# Alimentation.net
KiCad netlist of a schematic drawn in Altium Designer
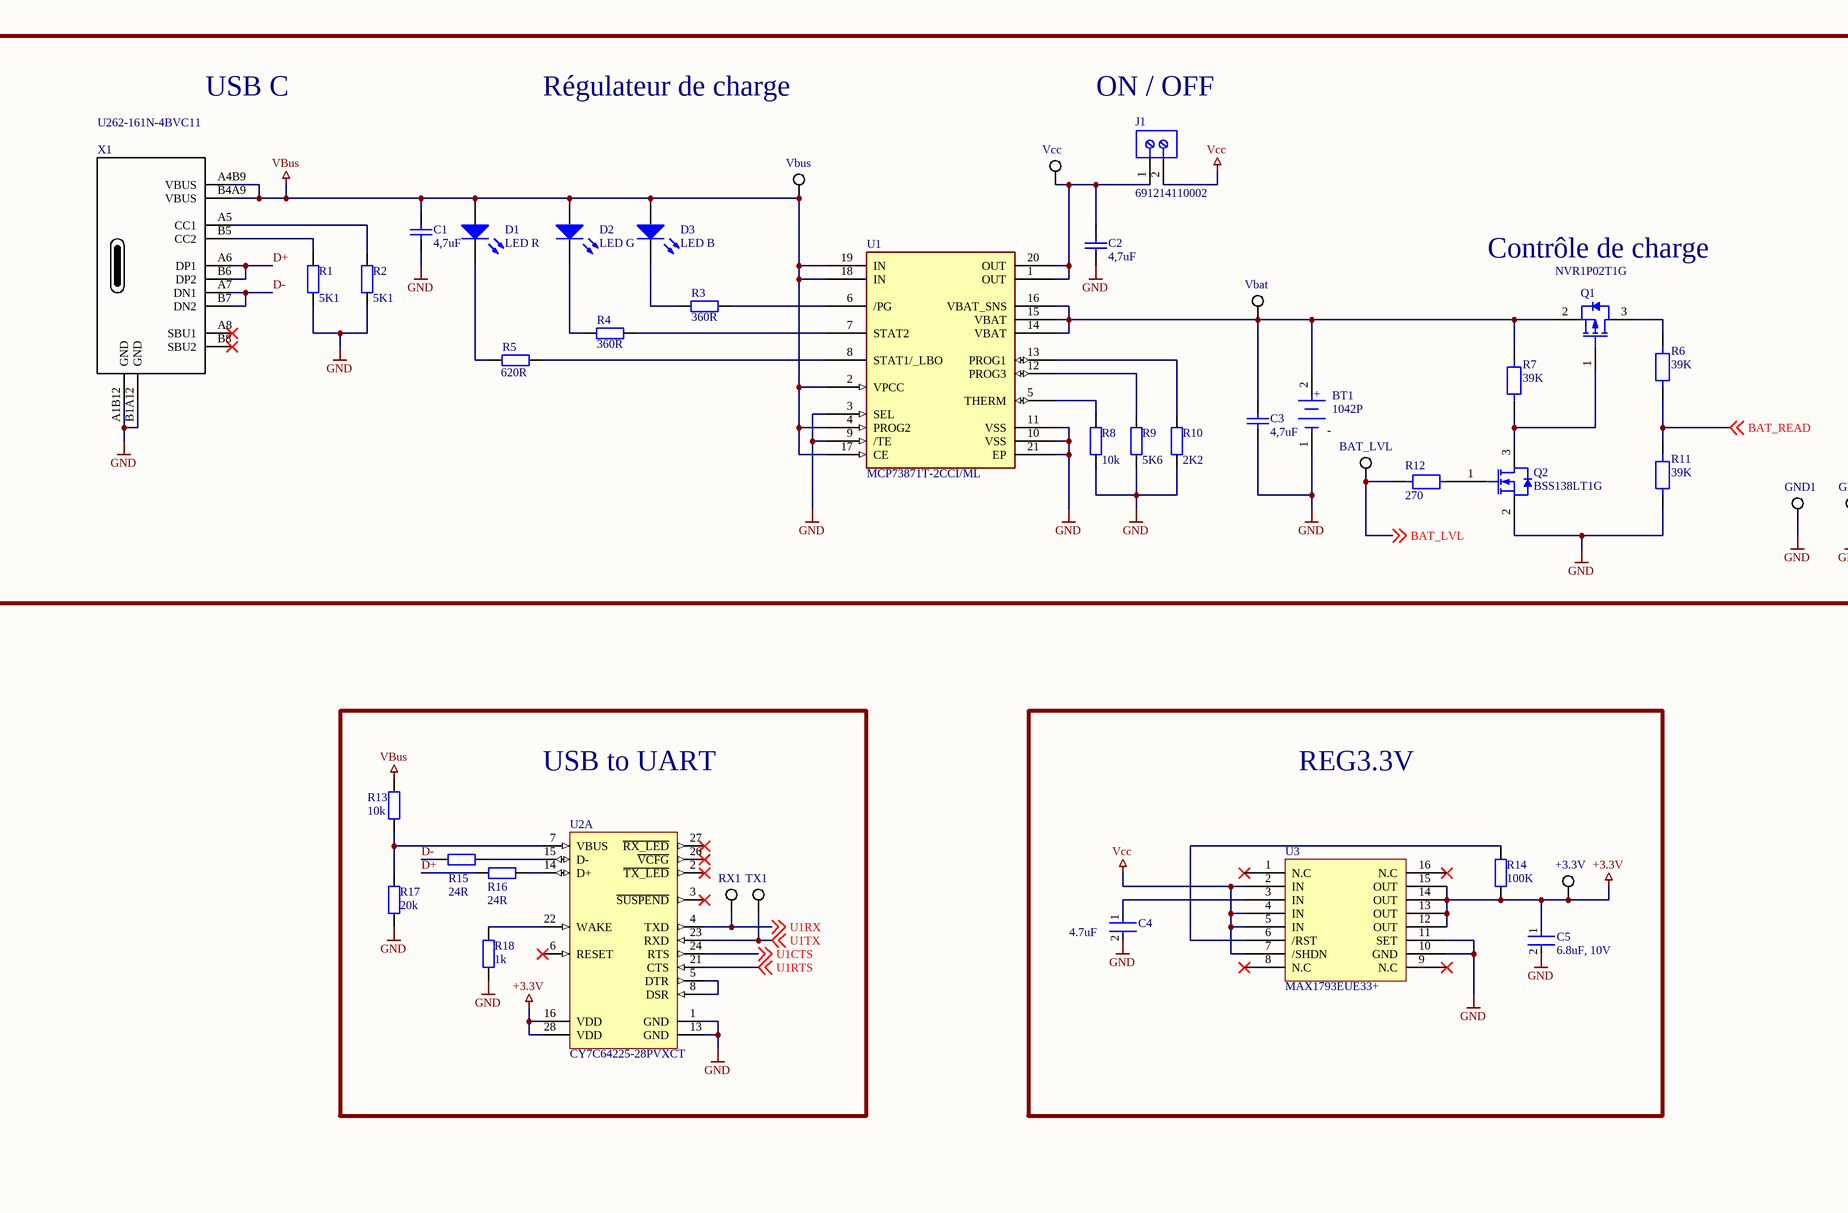
[diagram p0: Alimentation.SchDoc, left]
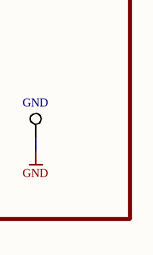
[diagram p1: Alimentation.SchDoc, right]

(export (version "E")
  (design (tool "Eeschema 10.0.6"))
  (components
    (comp (ref "+3.3V")
      (value "3.3V")
      (footprint "KSTN-5019_V")
      (description "Test Point, 1 Position SMD, RoHS, Tape and Reel")
      (libsource (lib "Altium Content Vault") (part "TESTPOINT_WHITE"))
    )
    (comp (ref "BAT_LVL")
      (value "Vbat")
      (footprint "KSTN-5019_V")
      (description "Test Point, 1 Position SMD, RoHS, Tape and Reel")
      (libsource (lib "Altium Content Vault") (part "TESTPOINT_WHITE"))
    )
    (comp (ref "BT1")
      (value "1042P")
      (footprint "FP-1042P-MFG")
      (description "BATTERY HOLDER 18650 SMD TAB")
      (libsource (lib "Altium Content Vault") (part "60d3b5b901a8747834971d0eb8cf3fd"))
    )
    (comp (ref "C1")
      (value "4,7uF")
      (footprint "CAP_0805")
      (description "Capacitor")
      (fields (field (name "PUBLISHER") "Altium Limited"))
      (libsource (lib "Miscellaneous Devices") (part "Cap"))
    )
    (comp (ref "C2")
      (value "4,7uF")
      (footprint "CAP_0805")
      (description "Capacitor")
      (fields (field (name "PUBLISHER") "Altium Limited"))
      (libsource (lib "Miscellaneous Devices") (part "Cap"))
    )
    (comp (ref "C3")
      (value "4,7uF")
      (footprint "CAP_0805")
      (description "Capacitor")
      (fields (field (name "PUBLISHER") "Altium Limited"))
      (libsource (lib "Miscellaneous Devices") (part "Cap"))
    )
    (comp (ref "C4")
      (value "4.7uF, 35V")
      (footprint "CAP_0805")
      (description "Multilayer Ceramic Capacitors 4.7μF ±10% 35V X7R SMD 0805")
      (fields (field (name "TOLERANCE") "10%") (field (name "CAPACITANCE") "4.7uF"))
      (libsource (lib "2121_Robot3roues_V2.0") (part "b4654b650e69147ec39a6b967a45e02"))
    )
    (comp (ref "C5")
      (value "6.8uF, 10V")
      (footprint "CAP_0805")
      (description "Cap Ceramic 6.8uF 10V X5R 20% Pad SMD 0805 +85°C Automotive T/R")
      (fields (field (name "TOLERANCE") "20%"))
      (libsource (lib "2121_Robot3roues_V2.0") (part "b4654b650e69147ec39a6b967a45e02"))
    )
    (comp (ref "D1")
      (value "LED R")
      (footprint "3.2X1.6X1.1")
      (description "Typical RED, GREEN, YELLOW, AMBER GaAs LED")
      (fields (field (name "PUBLISHER") "Altium Limited"))
      (libsource (lib "Miscellaneous Devices") (part "LED2"))
    )
    (comp (ref "D2")
      (value "LED G")
      (footprint "3.2X1.6X1.1")
      (description "Typical RED, GREEN, YELLOW, AMBER GaAs LED")
      (fields (field (name "PUBLISHER") "Altium Limited"))
      (libsource (lib "Miscellaneous Devices") (part "LED2"))
    )
    (comp (ref "D3")
      (value "LED B")
      (footprint "3.2X1.6X1.1")
      (description "Typical RED, GREEN, YELLOW, AMBER GaAs LED")
      (fields (field (name "PUBLISHER") "Altium Limited"))
      (libsource (lib "Miscellaneous Devices") (part "LED2"))
    )
    (comp (ref "GND")
      (value "Vbat")
      (footprint "KSTN-5019_V")
      (description "Test Point, 1 Position SMD, RoHS, Tape and Reel")
      (libsource (lib "Altium Content Vault") (part "TESTPOINT_WHITE"))
    )
    (comp (ref "GND1")
      (value "Vbat")
      (footprint "KSTN-5019_V")
      (description "Test Point, 1 Position SMD, RoHS, Tape and Reel")
      (libsource (lib "Altium Content Vault") (part "TESTPOINT_WHITE"))
    )
    (comp (ref "J1")
      (value "691214110002")
      (footprint "691214110002")
      (description "Serie 2141 - 3.50 mm Horizontal Entry Modular with Rising Cage Clamp WR-TBL, 2 pin")
      (fields (field (name "MANUFACTURER") "Wurth Elektronik") (field (name "PUBLISHER") "WurthElektronik"))
      (libsource (lib "Altium Content Vault") (part "WE-CN-1P-F-TB2"))
    )
    (comp (ref "Q1")
      (value "NVR1P02T1G")
      (footprint "ONSC-SOT-23-3-318-08_V")
      (description "Power MOSFET, -20 V, -1 A, P-Channel, 3-Pin SOT-23, Pb-Free, Tape and Reel")
      (fields (field (name "MANUFACTURER") "On Semiconductor"))
      (libsource (lib "Altium Content Vault") (part "ONSC-PMOS-G1S2D3-3_D"))
    )
    (comp (ref "Q2")
      (value "BSS138LT1G")
      (footprint "ONSC-SOT-23-3-318-08_V")
      (description "Power MOSFET, 200 mA, 50 V, N-Channel, 3-Pin SOT-23, Pb-Free, Tape and Reel")
      (fields (field (name "MANUFACTURER") "On Semiconductor"))
      (libsource (lib "Altium Content Vault") (part "ONSC-NMOS-G1S2D3-3"))
    )
    (comp (ref "R1")
      (value "5K1")
      (footprint "RES_0805")
      (description "Resistor")
      (fields (field (name "PUBLISHER") "Altium Limited"))
      (libsource (lib "Miscellaneous Devices") (part "Res2"))
    )
    (comp (ref "R2")
      (value "5K1")
      (footprint "RES_0805")
      (description "Resistor")
      (fields (field (name "PUBLISHER") "Altium Limited"))
      (libsource (lib "Miscellaneous Devices") (part "Res2"))
    )
    (comp (ref "R3")
      (value "360R")
      (footprint "RES_0805")
      (description "Resistor")
      (fields (field (name "PUBLISHER") "Altium Limited"))
      (libsource (lib "") (part "Res2_1"))
    )
    (comp (ref "R4")
      (value "360R")
      (footprint "RES_0805")
      (description "Resistor")
      (fields (field (name "PUBLISHER") "Altium Limited"))
      (libsource (lib "") (part "Res2_2"))
    )
    (comp (ref "R5")
      (value "620R")
      (footprint "RES_0805")
      (description "Resistor")
      (fields (field (name "PUBLISHER") "Altium Limited"))
      (libsource (lib "") (part "Res2_1"))
    )
    (comp (ref "R6")
      (value "39K")
      (footprint "RES_0805")
      (description "Resistor")
      (fields (field (name "PUBLISHER") "Altium Limited"))
      (libsource (lib "2122_RobotPenduleInverse_1") (part "Res3"))
    )
    (comp (ref "R7")
      (value "39K")
      (footprint "RES_0805")
      (description "Resistor")
      (fields (field (name "Comment") "36K") (field (name "PUBLISHER") "Altium Limited"))
      (libsource (lib "2122_RobotPenduleInverse_1") (part "Res3"))
    )
    (comp (ref "R8")
      (value "10k")
      (footprint "RES_0805")
      (description "Resistor")
      (fields (field (name "Comment") "10K") (field (name "PUBLISHER") "Altium Limited"))
      (libsource (lib "Miscellaneous Devices") (part "Res2"))
    )
    (comp (ref "R9")
      (value "5K6")
      (footprint "RES_0805")
      (description "Resistor")
      (fields (field (name "PUBLISHER") "Altium Limited"))
      (libsource (lib "Miscellaneous Devices") (part "Res2"))
    )
    (comp (ref "R10")
      (value "2K2")
      (footprint "RES_0805")
      (description "Resistor")
      (fields (field (name "PUBLISHER") "Altium Limited"))
      (libsource (lib "Miscellaneous Devices") (part "Res2"))
    )
    (comp (ref "R11")
      (value "39K")
      (footprint "RES_0805")
      (description "Resistor")
      (fields (field (name "PUBLISHER") "Altium Limited"))
      (libsource (lib "2122_RobotPenduleInverse_1") (part "Res3"))
    )
    (comp (ref "R12")
      (value "270")
      (footprint "RES_0805")
      (description "Resistor")
      (fields (field (name "Comment") "270R") (field (name "PUBLISHER") "Altium Limited"))
      (libsource (lib "2122_RobotPenduleInverse_1") (part "Res3"))
    )
    (comp (ref "R13")
      (value "10k")
      (footprint "RES_0805")
      (description "Resistor")
      (fields (field (name "Comment") "10K") (field (name "PUBLISHER") "Altium Limited"))
      (libsource (lib "Miscellaneous Devices") (part "Res2"))
    )
    (comp (ref "R14")
      (value "100K")
      (footprint "RES_0805")
      (fields (field (name "MANUFACTURER") "Panasonic") (field (name "PART NUMBER") "ERJ-P06J104V"))
      (libsource (lib "2121_Robot3roues_V2.0") (part "RES"))
    )
    (comp (ref "R15")
      (value "24R")
      (footprint "RES_0805")
      (description "Resistor")
      (fields (field (name "PUBLISHER") "Altium Limited"))
      (libsource (lib "") (part "Res2_1"))
    )
    (comp (ref "R16")
      (value "24R")
      (footprint "RES_0805")
      (description "Resistor")
      (fields (field (name "PUBLISHER") "Altium Limited"))
      (libsource (lib "") (part "Res2_1"))
    )
    (comp (ref "R17")
      (value "20k")
      (footprint "RES_0805")
      (description "Resistor")
      (fields (field (name "Comment") "20K") (field (name "PUBLISHER") "Altium Limited"))
      (libsource (lib "Miscellaneous Devices") (part "Res2"))
    )
    (comp (ref "R18")
      (value "1k")
      (footprint "RES_0805")
      (description "Resistor")
      (fields (field (name "Comment") "1K") (field (name "PUBLISHER") "Altium Limited"))
      (libsource (lib "Miscellaneous Devices") (part "Res2"))
    )
    (comp (ref "RX1")
      (value "Vbat")
      (footprint "KSTN-5019_V")
      (description "Test Point, 1 Position SMD, RoHS, Tape and Reel")
      (libsource (lib "Altium Content Vault") (part "TESTPOINT_WHITE"))
    )
    (comp (ref "TX1")
      (value "Vbat")
      (footprint "KSTN-5019_V")
      (description "Test Point, 1 Position SMD, RoHS, Tape and Reel")
      (libsource (lib "Altium Content Vault") (part "TESTPOINT_WHITE"))
    )
    (comp (ref "U1")
      (value "MCP73871T-2CCI/ML")
      (footprint "Microchip_C04V2")
      (description "Charger IC Lithium Ion/Polymer 20-QFN _4x4_")
      (fields (field (name "MF") "Microchip") (field (name "DIGI-KEY_PART_NUMBER") "MCP73871T-2CCI/MLCT-ND"))
      (libsource (lib "2121_Robot3roues") (part "MCP73871T-2CCI/ML"))
    )
    (comp (ref "U2")
      (value "CY7C64225-28PVXCT")
      (footprint "CYP-PVX28_M")
      (description "USB-to-UART Bridge Controller, 3 to 5.25 V, 0 to 70 degC, 28-Pin SSOP (PVX28), Tape and Reel")
      (fields (field (name "MANUFACTURER") "Cypress"))
      (libsource (lib "Altium Content Vault") (part "CYP-CY7C6422-PV28"))
    )
    (comp (ref "U3")
      (value "MAX1793EUE33+")
      (footprint "TSOP65P640X110_HS-17N")
      (libsource (lib "Robot3Roue") (part "MAX1793EUE33+"))
    )
    (comp (ref "Vbat")
      (value "Vbat")
      (footprint "KSTN-5019_V")
      (description "Test Point, 1 Position SMD, RoHS, Tape and Reel")
      (libsource (lib "Altium Content Vault") (part "TESTPOINT_WHITE"))
    )
    (comp (ref "Vbus")
      (value "Vbat")
      (footprint "KSTN-5019_V")
      (description "Test Point, 1 Position SMD, RoHS, Tape and Reel")
      (libsource (lib "Altium Content Vault") (part "TESTPOINT_WHITE"))
    )
    (comp (ref "Vcc")
      (value "Vbat")
      (footprint "KSTN-5019_V")
      (description "Test Point, 1 Position SMD, RoHS, Tape and Reel")
      (libsource (lib "Altium Content Vault") (part "TESTPOINT_WHITE"))
    )
    (comp (ref "X1")
      (value "U262-161N-4BVC11")
      (footprint "GCT_USB4105-GF-A")
      (description "U262-161N-4BVC11\r\n XKB Connectivity")
      (libsource (lib "Schlib1") (part "USB-C Type 2.0"))
    )
  )
  (nets
    (net (code "1") (name "+3.3V") (class "Default")
      (node (ref "+3.3V") (pin "1") (pinfunction "1_1") (pintype "passive"))
      (node (ref "C5") (pin "1") (pinfunction "1_1") (pintype "passive"))
      (node (ref "R14") (pin "1") (pinfunction "1_1") (pintype "passive"))
      (node (ref "U2") (pin "16") (pinfunction "VDD_16") (pintype "power_in"))
      (node (ref "U2") (pin "28") (pinfunction "VDD_28") (pintype "power_in"))
      (node (ref "U3") (pin "12") (pinfunction "OUT_12") (pintype "passive"))
      (node (ref "U3") (pin "13") (pinfunction "OUT_13") (pintype "passive"))
      (node (ref "U3") (pin "14") (pinfunction "OUT_14") (pintype "passive"))
      (node (ref "U3") (pin "15") (pinfunction "OUT_15") (pintype "passive"))
    )
    (net (code "2") (name "/D+") (class "Default")
      (node (ref "R16") (pin "1") (pinfunction "1_1") (pintype "passive"))
      (node (ref "X1") (pin "A6") (pinfunction "DP1_A6") (pintype "passive"))
      (node (ref "X1") (pin "B6") (pinfunction "DP2_B6") (pintype "passive"))
    )
    (net (code "3") (name "/D-") (class "Default")
      (node (ref "R15") (pin "1") (pinfunction "1_1") (pintype "passive"))
      (node (ref "X1") (pin "A7") (pinfunction "DN1_A7") (pintype "passive"))
      (node (ref "X1") (pin "B7") (pinfunction "DN2_B7") (pintype "passive"))
    )
    (net (code "4") (name "BAT_LVL") (class "Default")
      (node (ref "BAT_LVL") (pin "1") (pinfunction "1_1") (pintype "passive"))
      (node (ref "R12") (pin "1") (pinfunction "1_1") (pintype "passive"))
    )
    (net (code "5") (name "BAT_READ") (class "Default")
      (node (ref "R11") (pin "2") (pinfunction "2_2") (pintype "passive"))
      (node (ref "R6") (pin "1") (pinfunction "1_1") (pintype "passive"))
    )
    (net (code "6") (name "GND") (class "Default")
      (node (ref "BT1") (pin "1") (pinfunction "C_1") (pintype "passive"))
      (node (ref "C1") (pin "1") (pinfunction "1_1") (pintype "passive"))
      (node (ref "C2") (pin "1") (pinfunction "1_1") (pintype "passive"))
      (node (ref "C3") (pin "1") (pinfunction "1_1") (pintype "passive"))
      (node (ref "C4") (pin "2") (pinfunction "2_2") (pintype "passive"))
      (node (ref "C5") (pin "2") (pinfunction "2_2") (pintype "passive"))
      (node (ref "GND") (pin "1") (pinfunction "1_1") (pintype "passive"))
      (node (ref "GND1") (pin "1") (pinfunction "1_1") (pintype "passive"))
      (node (ref "Q2") (pin "2") (pinfunction "S_2") (pintype "passive"))
      (node (ref "R1") (pin "1") (pinfunction "1_1") (pintype "passive"))
      (node (ref "R10") (pin "1") (pinfunction "1_1") (pintype "passive"))
      (node (ref "R11") (pin "1") (pinfunction "1_1") (pintype "passive"))
      (node (ref "R17") (pin "1") (pinfunction "1_1") (pintype "passive"))
      (node (ref "R18") (pin "1") (pinfunction "1_1") (pintype "passive"))
      (node (ref "R2") (pin "1") (pinfunction "1_1") (pintype "passive"))
      (node (ref "R8") (pin "1") (pinfunction "1_1") (pintype "passive"))
      (node (ref "R9") (pin "1") (pinfunction "1_1") (pintype "passive"))
      (node (ref "U1") (pin "10") (pinfunction "VSS_10") (pintype "passive"))
      (node (ref "U1") (pin "11") (pinfunction "VSS_11") (pintype "passive"))
      (node (ref "U1") (pin "21") (pinfunction "EP_21") (pintype "passive"))
      (node (ref "U1") (pin "3") (pinfunction "SEL_3") (pintype "input"))
      (node (ref "U1") (pin "9") (pinfunction "/TE_9") (pintype "input"))
      (node (ref "U2") (pin "1") (pinfunction "GND_1") (pintype "power_in"))
      (node (ref "U2") (pin "13") (pinfunction "GND_13") (pintype "power_in"))
      (node (ref "U3") (pin "10") (pinfunction "GND_10") (pintype "passive"))
      (node (ref "U3") (pin "11") (pinfunction "SET_11") (pintype "passive"))
      (node (ref "X1") (pin "A1B12") (pinfunction "GND_A1B12") (pintype "passive"))
      (node (ref "X1") (pin "B1A12") (pinfunction "GND_B1A12") (pintype "passive"))
    )
    (net (code "7") (name "Net-(BT1-A)") (class "Default")
      (node (ref "BT1") (pin "2") (pinfunction "A_2") (pintype "passive"))
      (node (ref "C3") (pin "2") (pinfunction "2_2") (pintype "passive"))
      (node (ref "Q1") (pin "2") (pinfunction "S_2") (pintype "passive"))
      (node (ref "R7") (pin "2") (pinfunction "2_2") (pintype "passive"))
      (node (ref "U1") (pin "14") (pinfunction "VBAT_14") (pintype "passive"))
      (node (ref "U1") (pin "15") (pinfunction "VBAT_15") (pintype "passive"))
      (node (ref "U1") (pin "16") (pinfunction "VBAT_SNS_16") (pintype "passive"))
      (node (ref "Vbat") (pin "1") (pinfunction "1_1") (pintype "passive"))
    )
    (net (code "8") (name "Net-(C2-Pad2)") (class "Default")
      (node (ref "C2") (pin "2") (pinfunction "2_2") (pintype "passive"))
      (node (ref "J1") (pin "1") (pinfunction "1_1") (pintype "passive"))
      (node (ref "U1") (pin "1") (pinfunction "OUT_1") (pintype "passive"))
      (node (ref "U1") (pin "20") (pinfunction "OUT_20") (pintype "passive"))
      (node (ref "Vcc") (pin "1") (pinfunction "1_1") (pintype "passive"))
    )
    (net (code "9") (name "Net-(C4-Pad1)") (class "Default")
      (node (ref "C4") (pin "1") (pinfunction "1_1") (pintype "passive"))
      (node (ref "U3") (pin "3") (pinfunction "IN_3") (pintype "passive"))
    )
    (net (code "10") (name "Net-(D1-K)") (class "Default")
      (node (ref "D1") (pin "2") (pinfunction "K_2") (pintype "passive"))
      (node (ref "R5") (pin "1") (pinfunction "1_1") (pintype "passive"))
    )
    (net (code "11") (name "Net-(D2-K)") (class "Default")
      (node (ref "D2") (pin "2") (pinfunction "K_2") (pintype "passive"))
      (node (ref "R4") (pin "2") (pinfunction "2_2") (pintype "passive"))
    )
    (net (code "12") (name "Net-(D3-K)") (class "Default")
      (node (ref "D3") (pin "2") (pinfunction "K_2") (pintype "passive"))
      (node (ref "R3") (pin "1") (pinfunction "1_1") (pintype "passive"))
    )
    (net (code "13") (name "Net-(Q1-D)") (class "Default")
      (node (ref "Q1") (pin "3") (pinfunction "D_3") (pintype "passive"))
      (node (ref "R6") (pin "2") (pinfunction "2_2") (pintype "passive"))
    )
    (net (code "14") (name "Net-(Q1-G)") (class "Default")
      (node (ref "Q1") (pin "1") (pinfunction "G_1") (pintype "passive"))
      (node (ref "Q2") (pin "3") (pinfunction "D_3") (pintype "passive"))
      (node (ref "R7") (pin "1") (pinfunction "1_1") (pintype "passive"))
    )
    (net (code "15") (name "Net-(Q2-G)") (class "Default")
      (node (ref "Q2") (pin "1") (pinfunction "G_1") (pintype "passive"))
      (node (ref "R12") (pin "2") (pinfunction "2_2") (pintype "passive"))
    )
    (net (code "16") (name "Net-(U1-PROG1)") (class "Default")
      (node (ref "R10") (pin "2") (pinfunction "2_2") (pintype "passive"))
      (node (ref "U1") (pin "13") (pinfunction "PROG1_13") (pintype "bidirectional"))
    )
    (net (code "17") (name "Net-(U1-PROG3)") (class "Default")
      (node (ref "R9") (pin "2") (pinfunction "2_2") (pintype "passive"))
      (node (ref "U1") (pin "12") (pinfunction "PROG3_12") (pintype "bidirectional"))
    )
    (net (code "18") (name "Net-(U1-STAT1{slash}_LBO)") (class "Default")
      (node (ref "R5") (pin "2") (pinfunction "2_2") (pintype "passive"))
      (node (ref "U1") (pin "8") (pinfunction "STAT1/_LBO_8") (pintype "passive"))
    )
    (net (code "19") (name "Net-(U1-STAT2)") (class "Default")
      (node (ref "R4") (pin "1") (pinfunction "1_1") (pintype "passive"))
      (node (ref "U1") (pin "7") (pinfunction "STAT2_7") (pintype "passive"))
    )
    (net (code "20") (name "Net-(U1-THERM)") (class "Default")
      (node (ref "R8") (pin "2") (pinfunction "2_2") (pintype "passive"))
      (node (ref "U1") (pin "5") (pinfunction "THERM_5") (pintype "bidirectional"))
    )
    (net (code "21") (name "Net-(U1-{slash}PG)") (class "Default")
      (node (ref "R3") (pin "2") (pinfunction "2_2") (pintype "passive"))
      (node (ref "U1") (pin "6") (pinfunction "/PG_6") (pintype "passive"))
    )
    (net (code "22") (name "Net-(U2A-D+)") (class "Default")
      (node (ref "R16") (pin "2") (pinfunction "2_2") (pintype "passive"))
      (node (ref "U2") (pin "14") (pinfunction "D+_14") (pintype "bidirectional"))
    )
    (net (code "23") (name "Net-(U2A-D-)") (class "Default")
      (node (ref "R15") (pin "2") (pinfunction "2_2") (pintype "passive"))
      (node (ref "U2") (pin "15") (pinfunction "D-_15") (pintype "bidirectional"))
    )
    (net (code "24") (name "Net-(U2A-DSR)") (class "Default")
      (node (ref "U2") (pin "5") (pinfunction "DTR_5") (pintype "output"))
      (node (ref "U2") (pin "8") (pinfunction "DSR_8") (pintype "input"))
    )
    (net (code "25") (name "Net-(U2A-VBUS)") (class "Default")
      (node (ref "R13") (pin "1") (pinfunction "1_1") (pintype "passive"))
      (node (ref "R17") (pin "2") (pinfunction "2_2") (pintype "passive"))
      (node (ref "U2") (pin "7") (pinfunction "VBUS_7") (pintype "input"))
    )
    (net (code "26") (name "Net-(U2A-WAKE)") (class "Default")
      (node (ref "R18") (pin "2") (pinfunction "2_2") (pintype "passive"))
      (node (ref "U2") (pin "22") (pinfunction "WAKE_22") (pintype "input"))
    )
    (net (code "27") (name "Net-(U3-{slash}RST)") (class "Default")
      (node (ref "R14") (pin "2") (pinfunction "2_2") (pintype "passive"))
      (node (ref "U3") (pin "6") (pinfunction "/RST_6") (pintype "passive"))
    )
    (net (code "28") (name "Net-(X1-CC1)") (class "Default")
      (node (ref "R2") (pin "2") (pinfunction "2_2") (pintype "passive"))
      (node (ref "X1") (pin "A5") (pinfunction "CC1_A5") (pintype "passive"))
    )
    (net (code "29") (name "Net-(X1-CC2)") (class "Default")
      (node (ref "R1") (pin "2") (pinfunction "2_2") (pintype "passive"))
      (node (ref "X1") (pin "B5") (pinfunction "CC2_B5") (pintype "passive"))
    )
    (net (code "30") (name "U1CTS") (class "Default")
      (node (ref "U2") (pin "24") (pinfunction "RTS_24") (pintype "output"))
    )
    (net (code "31") (name "U1RTS") (class "Default")
      (node (ref "U2") (pin "21") (pinfunction "CTS_21") (pintype "input"))
    )
    (net (code "32") (name "U1RX") (class "Default")
      (node (ref "RX1") (pin "1") (pinfunction "1_1") (pintype "passive"))
      (node (ref "U2") (pin "4") (pinfunction "TXD_4") (pintype "output"))
    )
    (net (code "33") (name "U1TX") (class "Default")
      (node (ref "TX1") (pin "1") (pinfunction "1_1") (pintype "passive"))
      (node (ref "U2") (pin "23") (pinfunction "RXD_23") (pintype "input"))
    )
    (net (code "34") (name "VBus") (class "Default")
      (node (ref "C1") (pin "2") (pinfunction "2_2") (pintype "passive"))
      (node (ref "D1") (pin "1") (pinfunction "A_1") (pintype "passive"))
      (node (ref "D2") (pin "1") (pinfunction "A_1") (pintype "passive"))
      (node (ref "D3") (pin "1") (pinfunction "A_1") (pintype "passive"))
      (node (ref "R13") (pin "2") (pinfunction "2_2") (pintype "passive"))
      (node (ref "U1") (pin "17") (pinfunction "CE_17") (pintype "input"))
      (node (ref "U1") (pin "18") (pinfunction "IN_18") (pintype "passive"))
      (node (ref "U1") (pin "19") (pinfunction "IN_19") (pintype "passive"))
      (node (ref "U1") (pin "2") (pinfunction "VPCC_2") (pintype "input"))
      (node (ref "U1") (pin "4") (pinfunction "PROG2_4") (pintype "input"))
      (node (ref "Vbus") (pin "1") (pinfunction "1_1") (pintype "passive"))
      (node (ref "X1") (pin "A4B9") (pinfunction "VBUS_A4B9") (pintype "passive"))
      (node (ref "X1") (pin "B4A9") (pinfunction "VBUS_B4A9") (pintype "passive"))
    )
    (net (code "35") (name "Vcc") (class "Default")
      (node (ref "J1") (pin "2") (pinfunction "2_2") (pintype "passive"))
      (node (ref "U3") (pin "2") (pinfunction "IN_2") (pintype "passive"))
      (node (ref "U3") (pin "4") (pinfunction "IN_4") (pintype "passive"))
      (node (ref "U3") (pin "5") (pinfunction "IN_5") (pintype "passive"))
      (node (ref "U3") (pin "7") (pinfunction "/SHDN_7") (pintype "passive"))
    )
    (net (code "36") (name "unconnected-(U2A-RESET-Pad6)") (class "Default")
      (node (ref "U2") (pin "6") (pinfunction "RESET_6") (pintype "input+no_connect"))
    )
    (net (code "37") (name "unconnected-(U2A-~{RX_LED}-Pad27)") (class "Default")
      (node (ref "U2") (pin "27") (pinfunction "~{RX_LED}_27") (pintype "output+no_connect"))
    )
    (net (code "38") (name "unconnected-(U2A-~{SUSPEND}-Pad3)") (class "Default")
      (node (ref "U2") (pin "3") (pinfunction "~{SUSPEND}_3") (pintype "output+no_connect"))
    )
    (net (code "39") (name "unconnected-(U2A-~{TX_LED}-Pad2)") (class "Default")
      (node (ref "U2") (pin "2") (pinfunction "~{TX_LED}_2") (pintype "output+no_connect"))
    )
    (net (code "40") (name "unconnected-(U2A-~{VCFG}-Pad26)") (class "Default")
      (node (ref "U2") (pin "26") (pinfunction "~{VCFG}_26") (pintype "output+no_connect"))
    )
    (net (code "41") (name "unconnected-(U3-N.C-Pad1)") (class "Default")
      (node (ref "U3") (pin "1") (pinfunction "N.C_1") (pintype "passive+no_connect"))
    )
    (net (code "42") (name "unconnected-(U3-N.C-Pad8)") (class "Default")
      (node (ref "U3") (pin "8") (pinfunction "N.C_8") (pintype "passive+no_connect"))
    )
    (net (code "43") (name "unconnected-(U3-N.C-Pad9)") (class "Default")
      (node (ref "U3") (pin "9") (pinfunction "N.C_9") (pintype "passive+no_connect"))
    )
    (net (code "44") (name "unconnected-(U3-N.C-Pad16)") (class "Default")
      (node (ref "U3") (pin "16") (pinfunction "N.C_16") (pintype "passive+no_connect"))
    )
    (net (code "45") (name "unconnected-(X1-SBU1-PadA8)") (class "Default")
      (node (ref "X1") (pin "A8") (pinfunction "SBU1_A8") (pintype "passive+no_connect"))
    )
    (net (code "46") (name "unconnected-(X1-SBU2-PadB8)") (class "Default")
      (node (ref "X1") (pin "B8") (pinfunction "SBU2_B8") (pintype "passive+no_connect"))
    )
  )
)
